# v1.net
KiCad netlist of a schematic drawn in EAGLE
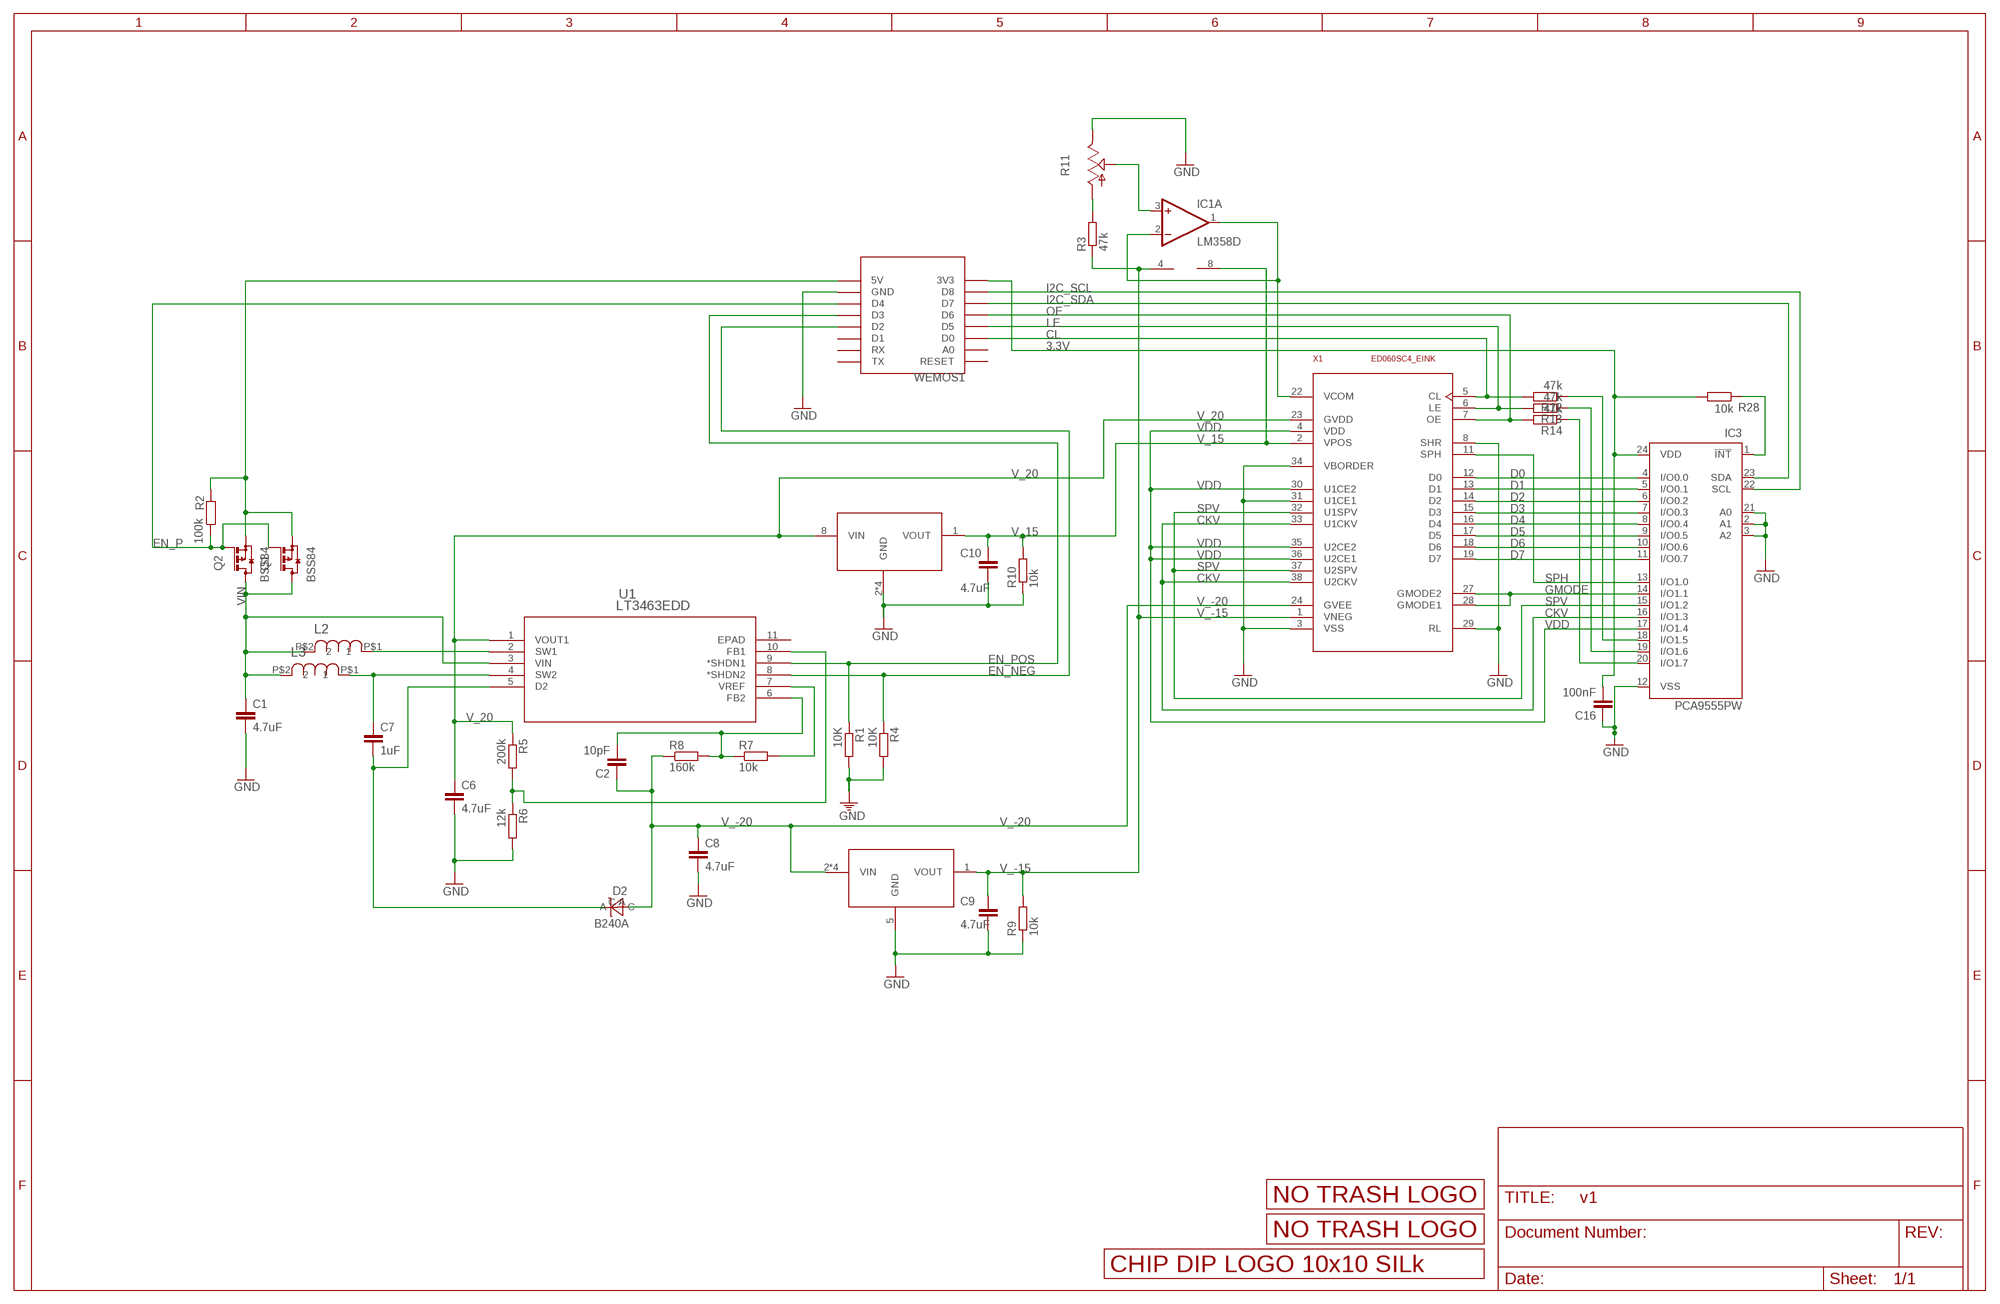
[diagram p0: schematic, sheet 1]

(export (version "E")
  (design (tool "Eeschema 10.0.6"))
  (components
    (comp (ref "C1")
      (value "4.7uF")
      (footprint "eagle-import:C0805")
      (libsource (lib "eagle-import") (part "C-EUC0805"))
    )
    (comp (ref "C2")
      (value "10pF")
      (footprint "eagle-import:C0805")
      (libsource (lib "eagle-import") (part "C-EUC0805"))
    )
    (comp (ref "C6")
      (value "4.7uF")
      (footprint "eagle-import:C0805")
      (libsource (lib "eagle-import") (part "C-EUC0805"))
    )
    (comp (ref "C7")
      (value "1uF")
      (footprint "eagle-import:C0805")
      (libsource (lib "eagle-import") (part "C-EUC0805"))
    )
    (comp (ref "C8")
      (value "4.7uF")
      (footprint "eagle-import:C0805")
      (libsource (lib "eagle-import") (part "C-EUC0805"))
    )
    (comp (ref "C9")
      (value "4.7uF")
      (footprint "eagle-import:C0805")
      (libsource (lib "eagle-import") (part "C-EUC0805"))
    )
    (comp (ref "C10")
      (value "4.7uF")
      (footprint "eagle-import:C0805")
      (libsource (lib "eagle-import") (part "C-EUC0805"))
    )
    (comp (ref "C16")
      (value "100nF")
      (footprint "eagle-import:C0805")
      (libsource (lib "eagle-import") (part "C-EUC0805"))
    )
    (comp (ref "D2")
      (value "B240A")
      (footprint "eagle-import:DO-214AC")
      (fields (field (name "MFG") "DIGIKEY") (field (name "VENDOR_PART_NUMBER") "B240A-13-F"))
      (libsource (lib "eagle-import") (part "DIODE_SCHTKY_B240"))
    )
    (comp (ref "IC1")
      (value "LM358D")
      (footprint "eagle-import:SO08")
      (libsource (lib "eagle-import") (part "LM358D"))
    )
    (comp (ref "IC3")
      (value "PCA9555PW")
      (footprint "eagle-import:TSSOP24")
      (libsource (lib "eagle-import") (part "PCA9555PW"))
    )
    (comp (ref "L2")
      (value "SRN6045-100M")
      (footprint "eagle-import:SRN6045")
      (fields (field (name "MFG") "DIGIKEY"))
      (libsource (lib "eagle-import") (part "SRN6045-100M"))
    )
    (comp (ref "L3")
      (value "SRN6045-100M")
      (footprint "eagle-import:SRN6045")
      (fields (field (name "MFG") "DIGIKEY"))
      (libsource (lib "eagle-import") (part "SRN6045-100M"))
    )
    (comp (ref "Q1")
      (value "BSS84")
      (footprint "eagle-import:SOT23")
      (libsource (lib "eagle-import") (part "BSS84"))
    )
    (comp (ref "Q2")
      (value "BSS84")
      (footprint "eagle-import:SOT23")
      (libsource (lib "eagle-import") (part "BSS84"))
    )
    (comp (ref "R1")
      (value "10K")
      (footprint "eagle-import:M0805")
      (libsource (lib "eagle-import") (part "R-EU_M0805"))
    )
    (comp (ref "R2")
      (value "100k")
      (footprint "eagle-import:R0805")
      (libsource (lib "eagle-import") (part "R-EU_R0805"))
    )
    (comp (ref "R3")
      (value "47k")
      (footprint "eagle-import:M0805")
      (libsource (lib "eagle-import") (part "R-EU_M0805"))
    )
    (comp (ref "R4")
      (value "10K")
      (footprint "eagle-import:M0805")
      (libsource (lib "eagle-import") (part "R-EU_M0805"))
    )
    (comp (ref "R5")
      (value "200k")
      (footprint "eagle-import:M0805")
      (libsource (lib "eagle-import") (part "R-EU_M0805"))
    )
    (comp (ref "R6")
      (value "12k")
      (footprint "eagle-import:M0805")
      (libsource (lib "eagle-import") (part "R-EU_M0805"))
    )
    (comp (ref "R7")
      (value "10k")
      (footprint "eagle-import:M0805")
      (libsource (lib "eagle-import") (part "R-EU_M0805"))
    )
    (comp (ref "R8")
      (value "160k")
      (footprint "eagle-import:M0805")
      (libsource (lib "eagle-import") (part "R-EU_M0805"))
    )
    (comp (ref "R9")
      (value "10k")
      (footprint "eagle-import:M0805")
      (libsource (lib "eagle-import") (part "R-EU_M0805"))
    )
    (comp (ref "R10")
      (value "10k")
      (footprint "eagle-import:M0805")
      (libsource (lib "eagle-import") (part "R-EU_M0805"))
    )
    (comp (ref "R11")
      (value "TRIM_US-SM-42/43X")
      (footprint "eagle-import:SM-42_43X")
      (libsource (lib "eagle-import") (part "TRIM_US-SM-42/43X"))
    )
    (comp (ref "R12")
      (value "47k")
      (footprint "eagle-import:M0805")
      (libsource (lib "eagle-import") (part "R-EU_M0805"))
    )
    (comp (ref "R13")
      (value "47k")
      (footprint "eagle-import:M0805")
      (libsource (lib "eagle-import") (part "R-EU_M0805"))
    )
    (comp (ref "R14")
      (value "47k")
      (footprint "eagle-import:M0805")
      (libsource (lib "eagle-import") (part "R-EU_M0805"))
    )
    (comp (ref "R28")
      (value "10k")
      (footprint "eagle-import:M0805")
      (libsource (lib "eagle-import") (part "R-EU_M0805"))
    )
    (comp (ref "U$1")
      (value "LM78L15ACMX")
      (footprint "eagle-import:SOIC127P600X175-8N")
      (libsource (lib "eagle-import") (part "LM78L15ACMX"))
    )
    (comp (ref "U$2")
      (value "LM79L15ACDG")
      (footprint "eagle-import:SOIC127P600X175-8N")
      (libsource (lib "eagle-import") (part "LM79L15ACDG"))
    )
    (comp (ref "U$3")
      (value "LOGO_10X10_SILK")
      (footprint "eagle-import:LOGO2_10X10_SILK")
      (libsource (lib "eagle-import") (part "LOGO_10X10_SILK"))
    )
    (comp (ref "U$4")
      (value "LOGO_NO_TRASHNO_TRASH")
      (footprint "eagle-import:LOGO_ROHS_NO_TRASH")
      (libsource (lib "eagle-import") (part "LOGO_NO_TRASHNO_TRASH"))
    )
    (comp (ref "U$5")
      (value "LOGO_NO_TRASHROHS")
      (footprint "eagle-import:LOGO_ROHS_SYM")
      (libsource (lib "eagle-import") (part "LOGO_NO_TRASHROHS"))
    )
    (comp (ref "U1")
      (value "LT3463EDD")
      (footprint "eagle-import:DFN-10_DD")
      (fields (field (name "MF") "Linear Technology"))
      (libsource (lib "eagle-import") (part "LT3463EDD"))
    )
    (comp (ref "WEMOS1")
      (value "WEMOS-D1-MINI")
      (footprint "eagle-import:WEMOS-D1-MINI")
      (libsource (lib "eagle-import") (part "WEMOS-D1-MINI"))
    )
    (comp (ref "X1")
      (value "ED060SC4_EINK")
      (footprint "eagle-import:FH26-39S-0.3SHW")
      (libsource (lib "eagle-import") (part "ED060SC4_EINK"))
    )
  )
  (nets
    (net (code "1") (name "/3.3V") (class "Default")
      (node (ref "C16") (pin "2") (pinfunction "2_2") (pintype "passive"))
      (node (ref "IC3") (pin "24") (pinfunction "VDD_24") (pintype "power_in"))
      (node (ref "R28") (pin "2") (pinfunction "2_2") (pintype "passive"))
      (node (ref "WEMOS1") (pin "3V3") (pinfunction "3V3_3V3") (pintype "bidirectional"))
    )
    (net (code "2") (name "/CKV") (class "Default")
      (node (ref "IC3") (pin "16") (pinfunction "I/O1.3_16") (pintype "bidirectional"))
      (node (ref "X1") (pin "33") (pinfunction "U1CKV_33") (pintype "bidirectional"))
      (node (ref "X1") (pin "38") (pinfunction "U2CKV_38") (pintype "bidirectional"))
    )
    (net (code "3") (name "/CL") (class "Default")
      (node (ref "R12") (pin "2") (pinfunction "2_2") (pintype "passive"))
      (node (ref "WEMOS1") (pin "D0") (pinfunction "D0_D0") (pintype "bidirectional"))
      (node (ref "X1") (pin "5") (pinfunction "CL_5") (pintype "bidirectional"))
    )
    (net (code "4") (name "/D0") (class "Default")
      (node (ref "IC3") (pin "4") (pinfunction "I/O0.0_4") (pintype "bidirectional"))
      (node (ref "X1") (pin "12") (pinfunction "D0_12") (pintype "bidirectional"))
    )
    (net (code "5") (name "/D1") (class "Default")
      (node (ref "IC3") (pin "5") (pinfunction "I/O0.1_5") (pintype "bidirectional"))
      (node (ref "X1") (pin "13") (pinfunction "D1_13") (pintype "bidirectional"))
    )
    (net (code "6") (name "/D2") (class "Default")
      (node (ref "IC3") (pin "6") (pinfunction "I/O0.2_6") (pintype "bidirectional"))
      (node (ref "X1") (pin "14") (pinfunction "D2_14") (pintype "bidirectional"))
    )
    (net (code "7") (name "/D3") (class "Default")
      (node (ref "IC3") (pin "7") (pinfunction "I/O0.3_7") (pintype "bidirectional"))
      (node (ref "X1") (pin "15") (pinfunction "D3_15") (pintype "bidirectional"))
    )
    (net (code "8") (name "/D4") (class "Default")
      (node (ref "IC3") (pin "8") (pinfunction "I/O0.4_8") (pintype "bidirectional"))
      (node (ref "X1") (pin "16") (pinfunction "D4_16") (pintype "bidirectional"))
    )
    (net (code "9") (name "/D5") (class "Default")
      (node (ref "IC3") (pin "9") (pinfunction "I/O0.5_9") (pintype "bidirectional"))
      (node (ref "X1") (pin "17") (pinfunction "D5_17") (pintype "bidirectional"))
    )
    (net (code "10") (name "/D6") (class "Default")
      (node (ref "IC3") (pin "10") (pinfunction "I/O0.6_10") (pintype "bidirectional"))
      (node (ref "X1") (pin "18") (pinfunction "D6_18") (pintype "bidirectional"))
    )
    (net (code "11") (name "/D7") (class "Default")
      (node (ref "IC3") (pin "11") (pinfunction "I/O0.7_11") (pintype "bidirectional"))
      (node (ref "X1") (pin "19") (pinfunction "D7_19") (pintype "bidirectional"))
    )
    (net (code "12") (name "/EN_NEG") (class "Default")
      (node (ref "R4") (pin "1") (pinfunction "1_1") (pintype "passive"))
      (node (ref "U1") (pin "8") (pinfunction "*SHDN2_8") (pintype "passive"))
      (node (ref "WEMOS1") (pin "D2") (pinfunction "D2_D2") (pintype "bidirectional"))
    )
    (net (code "13") (name "/EN_P") (class "Default")
      (node (ref "Q1") (pin "1") (pinfunction "G_1") (pintype "passive"))
      (node (ref "Q2") (pin "1") (pinfunction "G_1") (pintype "passive"))
      (node (ref "R2") (pin "1") (pinfunction "1_1") (pintype "passive"))
      (node (ref "WEMOS1") (pin "D4") (pinfunction "D4_D4") (pintype "bidirectional"))
    )
    (net (code "14") (name "/EN_POS") (class "Default")
      (node (ref "R1") (pin "1") (pinfunction "1_1") (pintype "passive"))
      (node (ref "U1") (pin "9") (pinfunction "*SHDN1_9") (pintype "passive"))
      (node (ref "WEMOS1") (pin "D3") (pinfunction "D3_D3") (pintype "bidirectional"))
    )
    (net (code "15") (name "/GMODE") (class "Default")
      (node (ref "IC3") (pin "14") (pinfunction "I/O1.1_14") (pintype "bidirectional"))
      (node (ref "X1") (pin "27") (pinfunction "GMODE2_27") (pintype "bidirectional"))
      (node (ref "X1") (pin "28") (pinfunction "GMODE1_28") (pintype "bidirectional"))
    )
    (net (code "16") (name "/I2C_SCL") (class "Default")
      (node (ref "IC3") (pin "22") (pinfunction "SCL_22") (pintype "input"))
      (node (ref "WEMOS1") (pin "D8") (pinfunction "D8_D8") (pintype "bidirectional"))
    )
    (net (code "17") (name "/I2C_SDA") (class "Default")
      (node (ref "IC3") (pin "23") (pinfunction "SDA_23") (pintype "bidirectional"))
      (node (ref "WEMOS1") (pin "D7") (pinfunction "D7_D7") (pintype "bidirectional"))
    )
    (net (code "18") (name "/LE") (class "Default")
      (node (ref "R13") (pin "2") (pinfunction "2_2") (pintype "passive"))
      (node (ref "WEMOS1") (pin "D5") (pinfunction "D5_D5") (pintype "bidirectional"))
      (node (ref "X1") (pin "6") (pinfunction "LE_6") (pintype "bidirectional"))
    )
    (net (code "19") (name "/OE") (class "Default")
      (node (ref "R14") (pin "2") (pinfunction "2_2") (pintype "passive"))
      (node (ref "WEMOS1") (pin "D6") (pinfunction "D6_D6") (pintype "bidirectional"))
      (node (ref "X1") (pin "7") (pinfunction "OE_7") (pintype "bidirectional"))
    )
    (net (code "20") (name "/SPH") (class "Default")
      (node (ref "IC3") (pin "13") (pinfunction "I/O1.0_13") (pintype "bidirectional"))
      (node (ref "X1") (pin "11") (pinfunction "SPH_11") (pintype "bidirectional"))
    )
    (net (code "21") (name "/SPV") (class "Default")
      (node (ref "IC3") (pin "15") (pinfunction "I/O1.2_15") (pintype "bidirectional"))
      (node (ref "X1") (pin "32") (pinfunction "U1SPV_32") (pintype "bidirectional"))
      (node (ref "X1") (pin "37") (pinfunction "U2SPV_37") (pintype "bidirectional"))
    )
    (net (code "22") (name "/VDD") (class "Default")
      (node (ref "IC3") (pin "17") (pinfunction "I/O1.4_17") (pintype "bidirectional"))
      (node (ref "X1") (pin "30") (pinfunction "U1CE2_30") (pintype "bidirectional"))
      (node (ref "X1") (pin "35") (pinfunction "U2CE2_35") (pintype "bidirectional"))
      (node (ref "X1") (pin "36") (pinfunction "U2CE1_36") (pintype "bidirectional"))
      (node (ref "X1") (pin "4") (pinfunction "VDD_4") (pintype "bidirectional"))
    )
    (net (code "23") (name "/VIN") (class "Default")
      (node (ref "C1") (pin "1") (pinfunction "1_1") (pintype "passive"))
      (node (ref "L2") (pin "P$2") (pinfunction "2_P$2") (pintype "passive"))
      (node (ref "L3") (pin "P$2") (pinfunction "2_P$2") (pintype "passive"))
      (node (ref "Q1") (pin "3") (pinfunction "D_3") (pintype "passive"))
      (node (ref "Q2") (pin "3") (pinfunction "D_3") (pintype "passive"))
      (node (ref "U1") (pin "3") (pinfunction "VIN_3") (pintype "input"))
    )
    (net (code "24") (name "/V_-15") (class "Default")
      (node (ref "C9") (pin "1") (pinfunction "1_1") (pintype "passive"))
      (node (ref "IC1") (pin "4") (pinfunction "V-_4") (pintype "power_in"))
      (node (ref "R3") (pin "1") (pinfunction "1_1") (pintype "passive"))
      (node (ref "R9") (pin "2") (pinfunction "2_2") (pintype "passive"))
      (node (ref "U$2") (pin "1") (pinfunction "VOUT_1") (pintype "bidirectional"))
      (node (ref "X1") (pin "1") (pinfunction "VNEG_1") (pintype "bidirectional"))
    )
    (net (code "25") (name "/V_-20") (class "Default")
      (node (ref "C2") (pin "1") (pinfunction "1_1") (pintype "passive"))
      (node (ref "C8") (pin "1") (pinfunction "1_1") (pintype "passive"))
      (node (ref "D2") (pin "A") (pinfunction "A_A") (pintype "bidirectional"))
      (node (ref "R8") (pin "1") (pinfunction "1_1") (pintype "passive"))
      (node (ref "U$2") (pin "2") (pinfunction "VIN_2") (pintype "bidirectional"))
      (node (ref "U$2") (pin "3") (pinfunction "VIN_3") (pintype "bidirectional"))
      (node (ref "U$2") (pin "6") (pinfunction "VIN_6") (pintype "bidirectional"))
      (node (ref "U$2") (pin "7") (pinfunction "VIN_7") (pintype "bidirectional"))
      (node (ref "X1") (pin "24") (pinfunction "GVEE_24") (pintype "bidirectional"))
    )
    (net (code "26") (name "/V_15") (class "Default")
      (node (ref "C10") (pin "1") (pinfunction "1_1") (pintype "passive"))
      (node (ref "IC1") (pin "8") (pinfunction "V+_8") (pintype "power_in"))
      (node (ref "R10") (pin "2") (pinfunction "2_2") (pintype "passive"))
      (node (ref "U$1") (pin "1") (pinfunction "VOUT_1") (pintype "bidirectional"))
      (node (ref "X1") (pin "2") (pinfunction "VPOS_2") (pintype "bidirectional"))
    )
    (net (code "27") (name "/V_20") (class "Default")
      (node (ref "C6") (pin "1") (pinfunction "1_1") (pintype "passive"))
      (node (ref "R5") (pin "1") (pinfunction "1_1") (pintype "passive"))
      (node (ref "U$1") (pin "8") (pinfunction "VIN_8") (pintype "bidirectional"))
      (node (ref "U1") (pin "1") (pinfunction "VOUT1_1") (pintype "output"))
      (node (ref "X1") (pin "23") (pinfunction "GVDD_23") (pintype "bidirectional"))
    )
    (net (code "28") (name "GND") (class "Default")
      (node (ref "C1") (pin "2") (pinfunction "2_2") (pintype "passive"))
      (node (ref "C10") (pin "2") (pinfunction "2_2") (pintype "passive"))
      (node (ref "C16") (pin "1") (pinfunction "1_1") (pintype "passive"))
      (node (ref "C6") (pin "2") (pinfunction "2_2") (pintype "passive"))
      (node (ref "C8") (pin "2") (pinfunction "2_2") (pintype "passive"))
      (node (ref "C9") (pin "2") (pinfunction "2_2") (pintype "passive"))
      (node (ref "IC3") (pin "12") (pinfunction "VSS_12") (pintype "power_in"))
      (node (ref "IC3") (pin "2") (pinfunction "A1_2") (pintype "input"))
      (node (ref "IC3") (pin "21") (pinfunction "A0_21") (pintype "input"))
      (node (ref "IC3") (pin "3") (pinfunction "A2_3") (pintype "input"))
      (node (ref "R1") (pin "2") (pinfunction "2_2") (pintype "passive"))
      (node (ref "R10") (pin "1") (pinfunction "1_1") (pintype "passive"))
      (node (ref "R11") (pin "3") (pinfunction "E_3") (pintype "passive"))
      (node (ref "R4") (pin "2") (pinfunction "2_2") (pintype "passive"))
      (node (ref "R6") (pin "2") (pinfunction "2_2") (pintype "passive"))
      (node (ref "R9") (pin "1") (pinfunction "1_1") (pintype "passive"))
      (node (ref "U$1") (pin "2") (pinfunction "GND_2") (pintype "bidirectional"))
      (node (ref "U$1") (pin "3") (pinfunction "GND_3") (pintype "bidirectional"))
      (node (ref "U$1") (pin "6") (pinfunction "GND_6") (pintype "bidirectional"))
      (node (ref "U$1") (pin "7") (pinfunction "GND_7") (pintype "bidirectional"))
      (node (ref "U$2") (pin "5") (pinfunction "GND_5") (pintype "bidirectional"))
      (node (ref "WEMOS1") (pin "GND") (pinfunction "GND_GND") (pintype "bidirectional"))
      (node (ref "X1") (pin "29") (pinfunction "RL_29") (pintype "bidirectional"))
      (node (ref "X1") (pin "3") (pinfunction "VSS_3") (pintype "bidirectional"))
      (node (ref "X1") (pin "31") (pinfunction "U1CE1_31") (pintype "bidirectional"))
      (node (ref "X1") (pin "34") (pinfunction "VBORDER_34") (pintype "bidirectional"))
      (node (ref "X1") (pin "8") (pinfunction "SHR_8") (pintype "bidirectional"))
    )
    (net (code "29") (name "Net-(IC1A-+IN)") (class "Default")
      (node (ref "IC1") (pin "3") (pinfunction "+IN_3") (pintype "input"))
      (node (ref "R11") (pin "2") (pinfunction "S_2") (pintype "passive"))
    )
    (net (code "30") (name "Net-(IC1A--IN)") (class "Default")
      (node (ref "IC1") (pin "1") (pinfunction "OUT_1") (pintype "output"))
      (node (ref "IC1") (pin "2") (pinfunction "-IN_2") (pintype "input"))
      (node (ref "X1") (pin "22") (pinfunction "VCOM_22") (pintype "bidirectional"))
    )
    (net (code "31") (name "Net-(IC3-I{slash}O1.5)") (class "Default")
      (node (ref "IC3") (pin "18") (pinfunction "I/O1.5_18") (pintype "bidirectional"))
      (node (ref "R12") (pin "1") (pinfunction "1_1") (pintype "passive"))
    )
    (net (code "32") (name "Net-(IC3-I{slash}O1.6)") (class "Default")
      (node (ref "IC3") (pin "19") (pinfunction "I/O1.6_19") (pintype "bidirectional"))
      (node (ref "R13") (pin "1") (pinfunction "1_1") (pintype "passive"))
    )
    (net (code "33") (name "Net-(IC3-I{slash}O1.7)") (class "Default")
      (node (ref "IC3") (pin "20") (pinfunction "I/O1.7_20") (pintype "bidirectional"))
      (node (ref "R14") (pin "1") (pinfunction "1_1") (pintype "passive"))
    )
    (net (code "34") (name "Net-(IC3-~{INT})") (class "Default")
      (node (ref "IC3") (pin "1") (pinfunction "~{INT}_1") (pintype "output"))
      (node (ref "R28") (pin "1") (pinfunction "1_1") (pintype "passive"))
    )
    (net (code "35") (name "Net-(L2-1)") (class "Default")
      (node (ref "L2") (pin "P$1") (pinfunction "1_P$1") (pintype "passive"))
      (node (ref "U1") (pin "2") (pinfunction "SW1_2") (pintype "passive"))
    )
    (net (code "36") (name "Net-(L3-1)") (class "Default")
      (node (ref "C7") (pin "1") (pinfunction "1_1") (pintype "passive"))
      (node (ref "L3") (pin "P$1") (pinfunction "1_P$1") (pintype "passive"))
      (node (ref "U1") (pin "4") (pinfunction "SW2_4") (pintype "passive"))
    )
    (net (code "37") (name "Net-(Q1-S)") (class "Default")
      (node (ref "Q1") (pin "2") (pinfunction "S_2") (pintype "passive"))
      (node (ref "Q2") (pin "2") (pinfunction "S_2") (pintype "passive"))
      (node (ref "R2") (pin "2") (pinfunction "2_2") (pintype "passive"))
      (node (ref "WEMOS1") (pin "5V") (pinfunction "5V_5V") (pintype "bidirectional"))
    )
    (net (code "38") (name "Net-(R11-A)") (class "Default")
      (node (ref "R11") (pin "1") (pinfunction "A_1") (pintype "passive"))
      (node (ref "R3") (pin "2") (pinfunction "2_2") (pintype "passive"))
    )
    (net (code "39") (name "Net-(U1-D2)") (class "Default")
      (node (ref "C7") (pin "2") (pinfunction "2_2") (pintype "passive"))
      (node (ref "D2") (pin "C") (pinfunction "C_C") (pintype "bidirectional"))
      (node (ref "U1") (pin "5") (pinfunction "D2_5") (pintype "passive"))
    )
    (net (code "40") (name "Net-(U1-FB1)") (class "Default")
      (node (ref "R5") (pin "2") (pinfunction "2_2") (pintype "passive"))
      (node (ref "R6") (pin "1") (pinfunction "1_1") (pintype "passive"))
      (node (ref "U1") (pin "10") (pinfunction "FB1_10") (pintype "output"))
    )
    (net (code "41") (name "Net-(U1-FB2)") (class "Default")
      (node (ref "C2") (pin "2") (pinfunction "2_2") (pintype "passive"))
      (node (ref "R7") (pin "1") (pinfunction "1_1") (pintype "passive"))
      (node (ref "R8") (pin "2") (pinfunction "2_2") (pintype "passive"))
      (node (ref "U1") (pin "6") (pinfunction "FB2_6") (pintype "passive"))
    )
    (net (code "42") (name "Net-(U1-VREF)") (class "Default")
      (node (ref "R7") (pin "2") (pinfunction "2_2") (pintype "passive"))
      (node (ref "U1") (pin "7") (pinfunction "VREF_7") (pintype "power_in"))
    )
    (net (code "43") (name "unconnected-(U1-EPAD-Pad11)") (class "Default")
      (node (ref "U1") (pin "11") (pinfunction "EPAD_11") (pintype "passive"))
    )
    (net (code "44") (name "unconnected-(WEMOS1-PadA0)") (class "Default")
      (node (ref "WEMOS1") (pin "A0") (pinfunction "A0_A0") (pintype "bidirectional"))
    )
    (net (code "45") (name "unconnected-(WEMOS1-PadD1)") (class "Default")
      (node (ref "WEMOS1") (pin "D1") (pinfunction "D1_D1") (pintype "bidirectional"))
    )
    (net (code "46") (name "unconnected-(WEMOS1-PadRESET)") (class "Default")
      (node (ref "WEMOS1") (pin "RESET") (pinfunction "RESET_RESET") (pintype "bidirectional"))
    )
    (net (code "47") (name "unconnected-(WEMOS1-PadRX)") (class "Default")
      (node (ref "WEMOS1") (pin "RX") (pinfunction "RX_RX") (pintype "bidirectional"))
    )
    (net (code "48") (name "unconnected-(WEMOS1-PadTX)") (class "Default")
      (node (ref "WEMOS1") (pin "TX") (pinfunction "TX_TX") (pintype "bidirectional"))
    )
  )
)
